# SignalMast-ColorLight-SingleHead.net
KiCad netlist of a schematic drawn in EAGLE
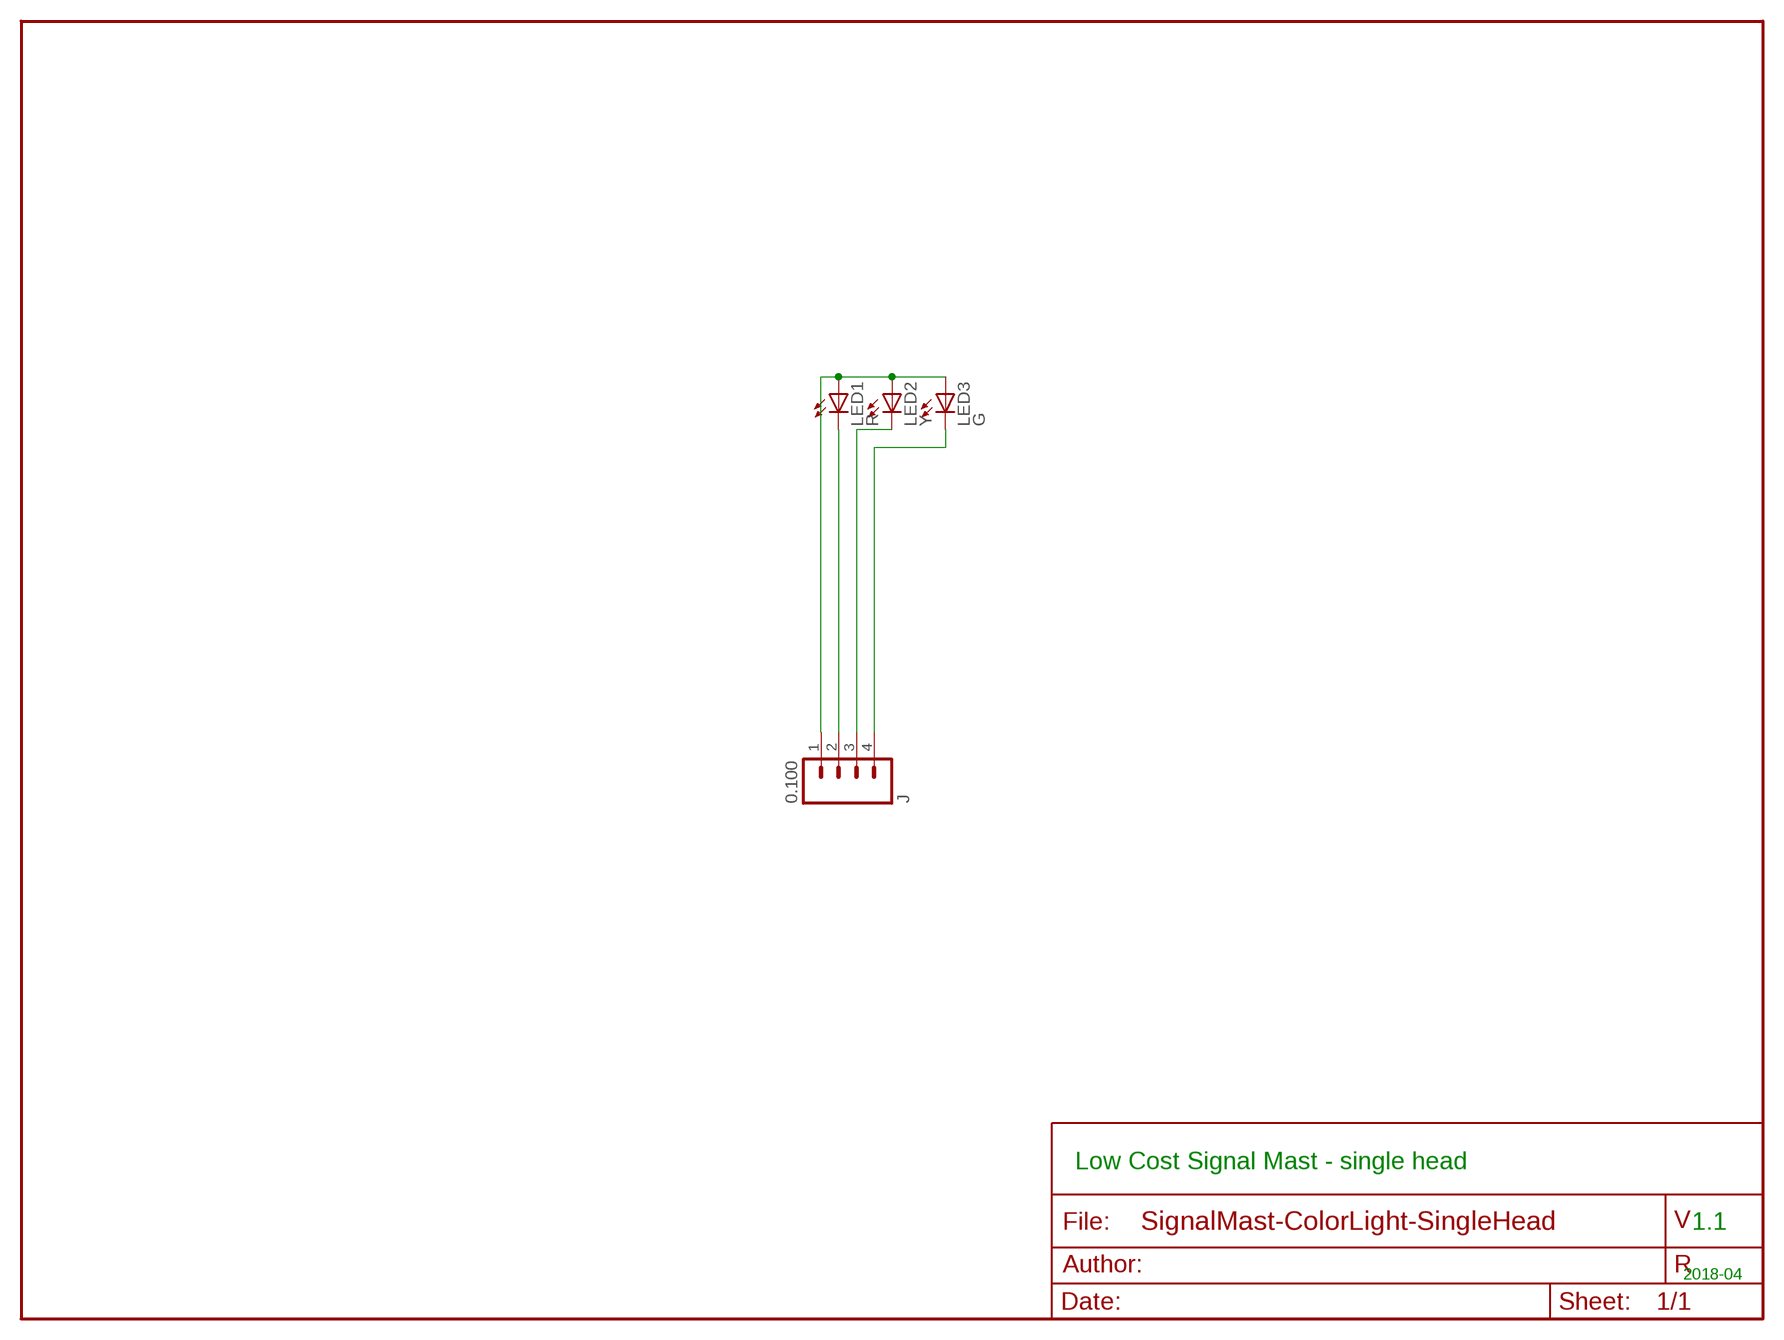
[diagram p0: schematic, sheet 1]

(export (version "E")
  (design (tool "Eeschema 10.0.6"))
  (components
    (comp (ref "J")
      (value "0.100")
      (footprint "eagle-import:1X04_LOCK")
      (libsource (lib "eagle-import") (part "CONNECTOR-M04LOCK"))
    )
    (comp (ref "LED1")
      (value "R")
      (footprint "eagle-import:0603-LED")
      (libsource (lib "eagle-import") (part "LED0603-LED"))
    )
    (comp (ref "LED2")
      (value "Y")
      (footprint "eagle-import:0603-LED")
      (libsource (lib "eagle-import") (part "LED0603-LED"))
    )
    (comp (ref "LED3")
      (value "G")
      (footprint "eagle-import:0603-LED")
      (libsource (lib "eagle-import") (part "LED0603-LED"))
    )
  )
  (nets
    (net (code "1") (name "Net-(J-Pad1)") (class "Default")
      (node (ref "J") (pin "1") (pinfunction "1_1") (pintype "passive"))
      (node (ref "LED1") (pin "A") (pinfunction "A_A") (pintype "passive"))
      (node (ref "LED2") (pin "A") (pinfunction "A_A") (pintype "passive"))
      (node (ref "LED3") (pin "A") (pinfunction "A_A") (pintype "passive"))
    )
    (net (code "2") (name "Net-(J-Pad2)") (class "Default")
      (node (ref "J") (pin "2") (pinfunction "2_2") (pintype "passive"))
      (node (ref "LED1") (pin "C") (pinfunction "C_C") (pintype "passive"))
    )
    (net (code "3") (name "Net-(J-Pad3)") (class "Default")
      (node (ref "J") (pin "3") (pinfunction "3_3") (pintype "passive"))
      (node (ref "LED2") (pin "C") (pinfunction "C_C") (pintype "passive"))
    )
    (net (code "4") (name "Net-(J-Pad4)") (class "Default")
      (node (ref "J") (pin "4") (pinfunction "4_4") (pintype "passive"))
      (node (ref "LED3") (pin "C") (pinfunction "C_C") (pintype "passive"))
    )
  )
)
